# PCB_Source.net
KiCad netlist of a schematic drawn in EasyEDA Pro
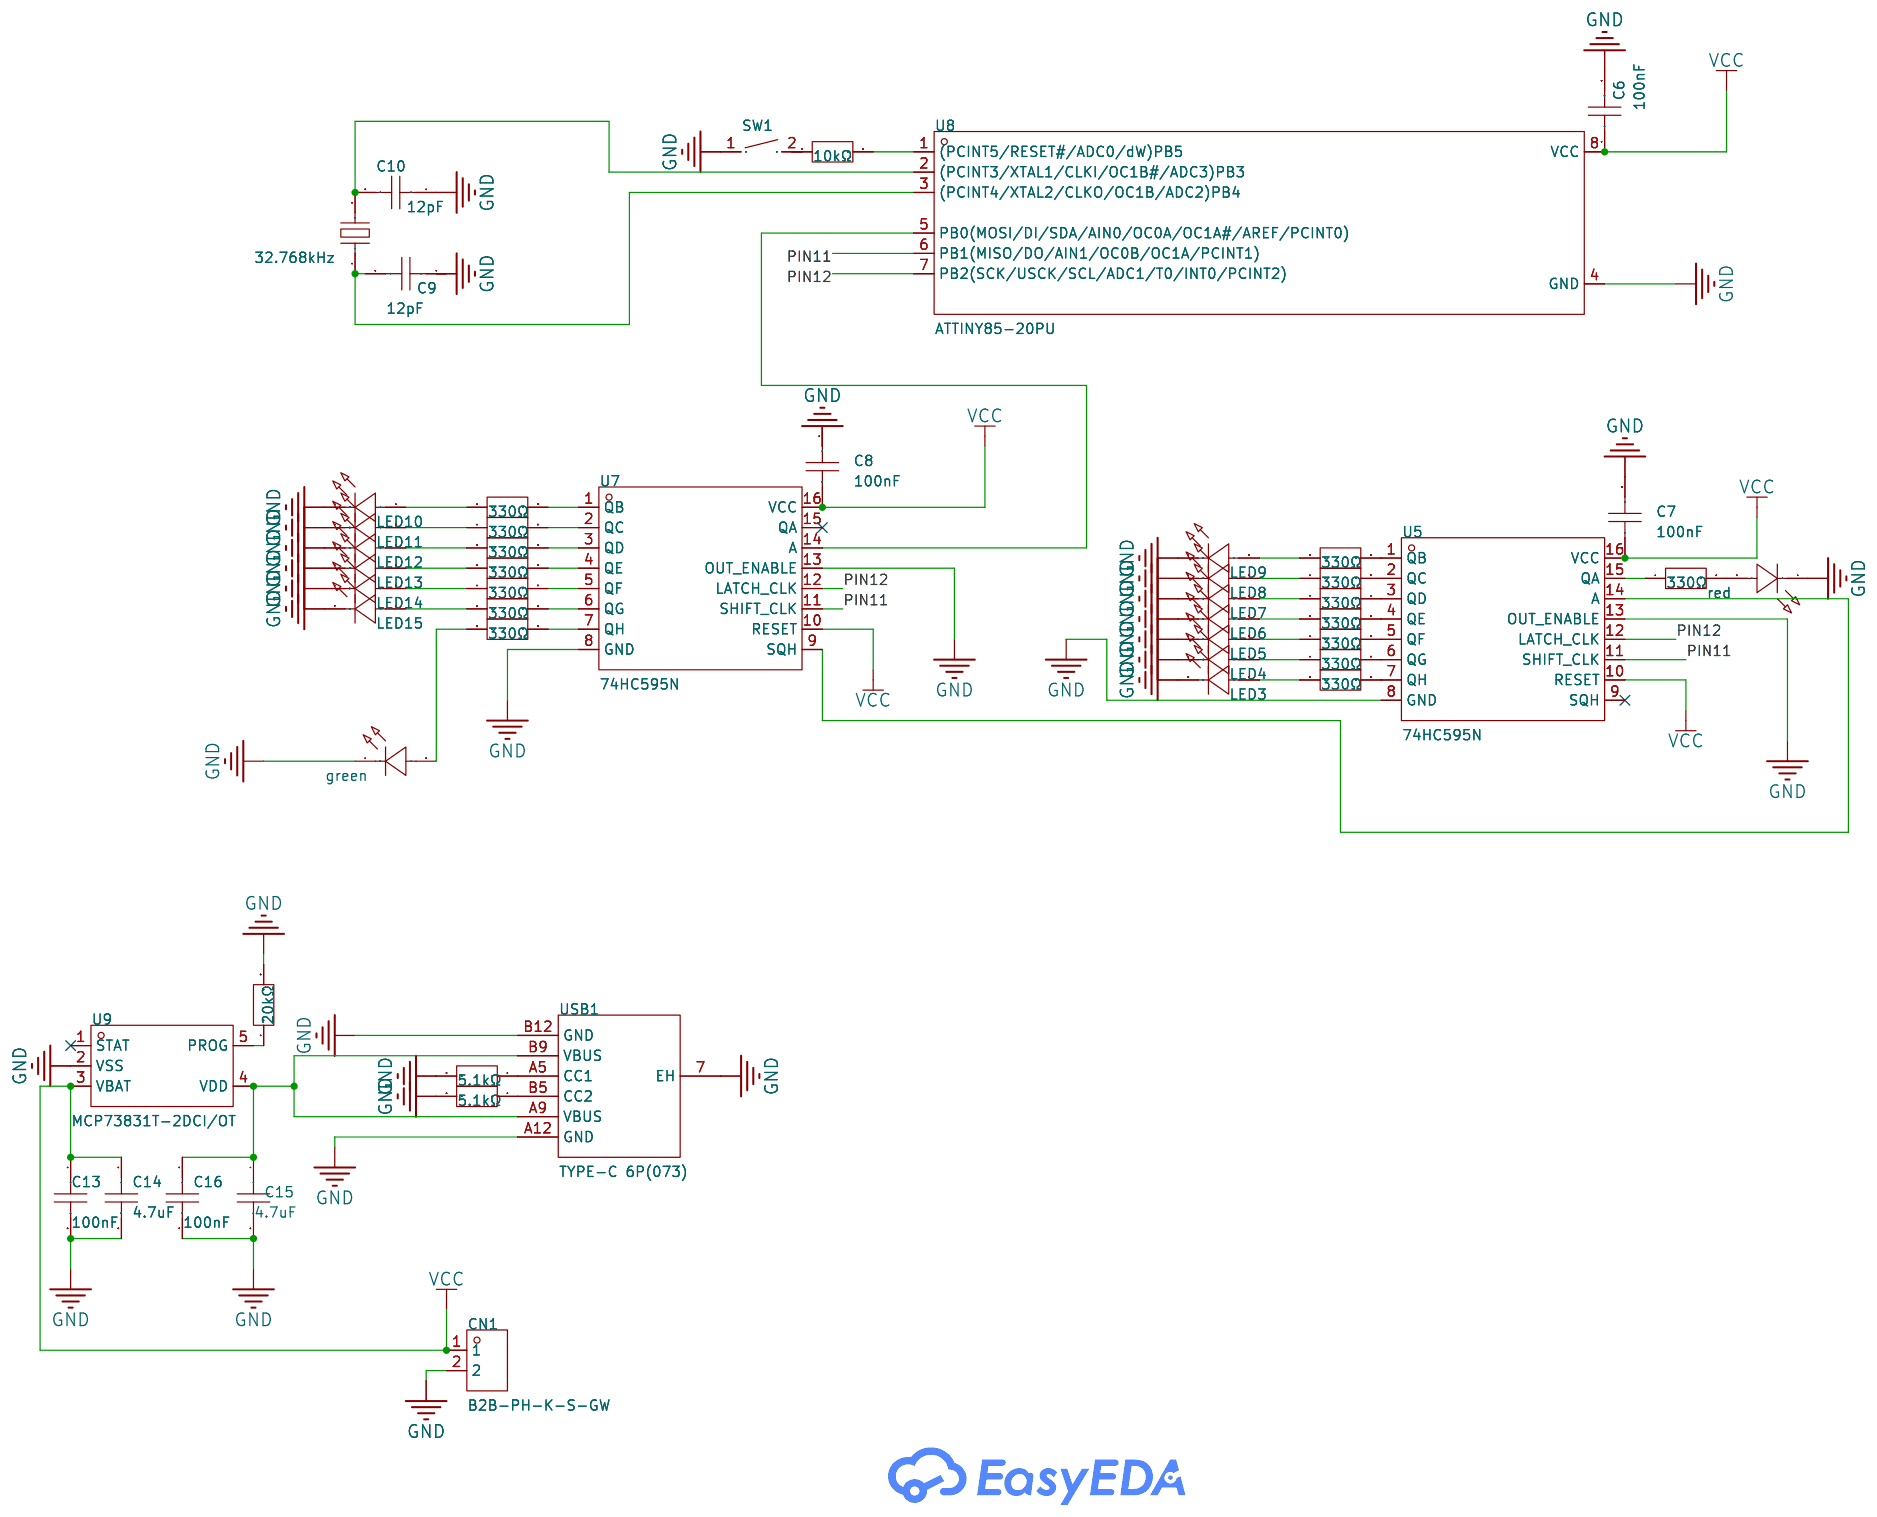
[diagram p0: schematic sheet]

(export (version "E")
  (design (tool "Eeschema 10.0.6"))
  (components
    (comp (ref "C6")
      (value "100nF")
      (footprint "easyedapro:CAP-TH_L5.8-W2.4-P2.54-D0.6")
      (fields
        (field (name "Manufacturer Part") "CC1H104ZA1ED3F5P1100")
        (field (name "Manufacturer") "Dersonic(德尔创)")
      )
      (libsource (lib "easyedapro") (part "CC1H104ZA1ED3F5P1100"))
    )
    (comp (ref "C7")
      (value "100nF")
      (footprint "easyedapro:CAP-TH_L5.8-W2.4-P2.54-D0.6")
      (fields
        (field (name "Manufacturer Part") "CC1H104ZA1ED3F5P1100")
        (field (name "Manufacturer") "Dersonic(德尔创)")
      )
      (libsource (lib "easyedapro") (part "CC1H104ZA1ED3F5P1100"))
    )
    (comp (ref "C8")
      (value "100nF")
      (footprint "easyedapro:CAP-TH_L5.8-W2.4-P2.54-D0.6")
      (fields
        (field (name "Manufacturer Part") "CC1H104ZA1ED3F5P1100")
        (field (name "Manufacturer") "Dersonic(德尔创)")
      )
      (libsource (lib "easyedapro") (part "CC1H104ZA1ED3F5P1100"))
    )
    (comp (ref "C9")
      (value "12pF")
      (footprint "easyedapro:CAP-TH_L5.8-W2.4-P2.54-D0.6")
      (fields
        (field (name "Manufacturer Part") "CC1H104ZA1ED3F5P1100")
        (field (name "Manufacturer") "Dersonic(德尔创)")
      )
      (libsource (lib "easyedapro") (part "CC1H104ZA1ED3F5P1100"))
    )
    (comp (ref "C10")
      (value "12pF")
      (footprint "easyedapro:CAP-TH_L5.8-W2.4-P2.54-D0.6")
      (fields
        (field (name "Manufacturer Part") "CC1H104ZA1ED3F5P1100")
        (field (name "Manufacturer") "Dersonic(德尔创)")
      )
      (libsource (lib "easyedapro") (part "CC1H104ZA1ED3F5P1100"))
    )
    (comp (ref "C13")
      (value "100nF")
      (footprint "easyedapro:CAP-TH_L5.8-W2.4-P2.54-D0.6")
      (fields
        (field (name "Manufacturer Part") "CC1H104ZA1ED3F5P1100")
        (field (name "Manufacturer") "Dersonic(德尔创)")
      )
      (libsource (lib "easyedapro") (part "CC1H104ZA1ED3F5P1100"))
    )
    (comp (ref "C14")
      (value "4.7uF")
      (footprint "easyedapro:CAP-TH_L5.8-W2.4-P2.54-D0.6")
      (fields
        (field (name "Manufacturer Part") "CC1H104ZA1ED3F5P1100")
        (field (name "Manufacturer") "Dersonic(德尔创)")
      )
      (libsource (lib "easyedapro") (part "CC1H104ZA1ED3F5P1100"))
    )
    (comp (ref "C15")
      (value "4.7uF")
      (footprint "easyedapro:CAP-TH_L5.8-W2.4-P2.54-D0.6")
      (fields
        (field (name "Manufacturer Part") "CC1H104ZA1ED3F5P1100")
        (field (name "Manufacturer") "Dersonic(德尔创)")
      )
      (libsource (lib "easyedapro") (part "CC1H104ZA1ED3F5P1100"))
    )
    (comp (ref "C16")
      (value "100nF")
      (footprint "easyedapro:CAP-TH_L5.8-W2.4-P2.54-D0.6")
      (fields
        (field (name "Manufacturer Part") "CC1H104ZA1ED3F5P1100")
        (field (name "Manufacturer") "Dersonic(德尔创)")
      )
      (libsource (lib "easyedapro") (part "CC1H104ZA1ED3F5P1100"))
    )
    (comp (ref "CN1")
      (value "B2B-PH-K-S-GW")
      (footprint "easyedapro:CONN-TH_B2B-PH-K-S")
      (fields (field (name "Manufacturer") "JST"))
      (libsource (lib "easyedapro") (part "B2B-PH-K-S-GW"))
    )
    (comp (ref "green")
      (value "TJ-S2012EX8T5ALC2R-A5")
      (footprint "easyedapro:LED0805-RD")
      (fields (field (name "Manufacturer") "TOGIALED(统佳)"))
      (libsource (lib "easyedapro") (part "TJ-S2012EX8T5ALC2R-A5"))
    )
    (comp (ref "LED3")
      (value "TJ-S2012EX8T5ALC2R-A5")
      (footprint "easyedapro:LED0805-RD")
      (fields (field (name "Manufacturer") "TOGIALED(统佳)"))
      (libsource (lib "easyedapro") (part "TJ-S2012EX8T5ALC2R-A5"))
    )
    (comp (ref "LED4")
      (value "TJ-S2012EX8T5ALC2R-A5")
      (footprint "easyedapro:LED0805-RD")
      (fields (field (name "Manufacturer") "TOGIALED(统佳)"))
      (libsource (lib "easyedapro") (part "TJ-S2012EX8T5ALC2R-A5"))
    )
    (comp (ref "LED5")
      (value "TJ-S2012EX8T5ALC2R-A5")
      (footprint "easyedapro:LED0805-RD")
      (fields (field (name "Manufacturer") "TOGIALED(统佳)"))
      (libsource (lib "easyedapro") (part "TJ-S2012EX8T5ALC2R-A5"))
    )
    (comp (ref "LED6")
      (value "TJ-S2012EX8T5ALC2R-A5")
      (footprint "easyedapro:LED0805-RD")
      (fields (field (name "Manufacturer") "TOGIALED(统佳)"))
      (libsource (lib "easyedapro") (part "TJ-S2012EX8T5ALC2R-A5"))
    )
    (comp (ref "LED7")
      (value "TJ-S2012EX8T5ALC2R-A5")
      (footprint "easyedapro:LED0805-RD")
      (fields (field (name "Manufacturer") "TOGIALED(统佳)"))
      (libsource (lib "easyedapro") (part "TJ-S2012EX8T5ALC2R-A5"))
    )
    (comp (ref "LED8")
      (value "TJ-S2012EX8T5ALC2R-A5")
      (footprint "easyedapro:LED0805-RD")
      (fields (field (name "Manufacturer") "TOGIALED(统佳)"))
      (libsource (lib "easyedapro") (part "TJ-S2012EX8T5ALC2R-A5"))
    )
    (comp (ref "LED9")
      (value "TJ-S2012EX8T5ALC2R-A5")
      (footprint "easyedapro:LED0805-RD")
      (fields (field (name "Manufacturer") "TOGIALED(统佳)"))
      (libsource (lib "easyedapro") (part "TJ-S2012EX8T5ALC2R-A5"))
    )
    (comp (ref "LED10")
      (value "TJ-S2012EX8T5ALC2R-A5")
      (footprint "easyedapro:LED0805-RD")
      (fields (field (name "Manufacturer") "TOGIALED(统佳)"))
      (libsource (lib "easyedapro") (part "TJ-S2012EX8T5ALC2R-A5"))
    )
    (comp (ref "LED11")
      (value "TJ-S2012EX8T5ALC2R-A5")
      (footprint "easyedapro:LED0805-RD")
      (fields (field (name "Manufacturer") "TOGIALED(统佳)"))
      (libsource (lib "easyedapro") (part "TJ-S2012EX8T5ALC2R-A5"))
    )
    (comp (ref "LED12")
      (value "TJ-S2012EX8T5ALC2R-A5")
      (footprint "easyedapro:LED0805-RD")
      (fields (field (name "Manufacturer") "TOGIALED(统佳)"))
      (libsource (lib "easyedapro") (part "TJ-S2012EX8T5ALC2R-A5"))
    )
    (comp (ref "LED13")
      (value "TJ-S2012EX8T5ALC2R-A5")
      (footprint "easyedapro:LED0805-RD")
      (fields (field (name "Manufacturer") "TOGIALED(统佳)"))
      (libsource (lib "easyedapro") (part "TJ-S2012EX8T5ALC2R-A5"))
    )
    (comp (ref "LED14")
      (value "TJ-S2012EX8T5ALC2R-A5")
      (footprint "easyedapro:LED0805-RD")
      (fields (field (name "Manufacturer") "TOGIALED(统佳)"))
      (libsource (lib "easyedapro") (part "TJ-S2012EX8T5ALC2R-A5"))
    )
    (comp (ref "LED15")
      (value "TJ-S2012EX8T5ALC2R-A5")
      (footprint "easyedapro:LED0805-RD")
      (fields (field (name "Manufacturer") "TOGIALED(统佳)"))
      (libsource (lib "easyedapro") (part "TJ-S2012EX8T5ALC2R-A5"))
    )
    (comp (ref "R20")
      (value "330Ω")
      (footprint "easyedapro:RES-TH_BD2.3-L6.5-P10.50-D0.5")
      (fields (field (name "Manufacturer Part") "MF1/4W-1KΩ±1%T52") (field (name "Manufacturer") "华星机电"))
      (libsource (lib "easyedapro") (part "MF1/4W-1KΩ±1%T52"))
    )
    (comp (ref "R21")
      (value "330Ω")
      (footprint "easyedapro:RES-TH_BD2.3-L6.5-P10.50-D0.5")
      (fields (field (name "Manufacturer Part") "MF1/4W-1KΩ±1%T52") (field (name "Manufacturer") "华星机电"))
      (libsource (lib "easyedapro") (part "MF1/4W-1KΩ±1%T52"))
    )
    (comp (ref "R22")
      (value "330Ω")
      (footprint "easyedapro:RES-TH_BD2.3-L6.5-P10.50-D0.5")
      (fields (field (name "Manufacturer Part") "MF1/4W-1KΩ±1%T52") (field (name "Manufacturer") "华星机电"))
      (libsource (lib "easyedapro") (part "MF1/4W-1KΩ±1%T52"))
    )
    (comp (ref "R23")
      (value "330Ω")
      (footprint "easyedapro:RES-TH_BD2.3-L6.5-P10.50-D0.5")
      (fields (field (name "Manufacturer Part") "MF1/4W-1KΩ±1%T52") (field (name "Manufacturer") "华星机电"))
      (libsource (lib "easyedapro") (part "MF1/4W-1KΩ±1%T52"))
    )
    (comp (ref "R24")
      (value "330Ω")
      (footprint "easyedapro:RES-TH_BD2.3-L6.5-P10.50-D0.5")
      (fields (field (name "Manufacturer Part") "MF1/4W-1KΩ±1%T52") (field (name "Manufacturer") "华星机电"))
      (libsource (lib "easyedapro") (part "MF1/4W-1KΩ±1%T52"))
    )
    (comp (ref "R25")
      (value "330Ω")
      (footprint "easyedapro:RES-TH_BD2.3-L6.5-P10.50-D0.5")
      (fields (field (name "Manufacturer Part") "MF1/4W-1KΩ±1%T52") (field (name "Manufacturer") "华星机电"))
      (libsource (lib "easyedapro") (part "MF1/4W-1KΩ±1%T52"))
    )
    (comp (ref "R26")
      (value "330Ω")
      (footprint "easyedapro:RES-TH_BD2.3-L6.5-P10.50-D0.5")
      (fields (field (name "Manufacturer Part") "MF1/4W-1KΩ±1%T52") (field (name "Manufacturer") "华星机电"))
      (libsource (lib "easyedapro") (part "MF1/4W-1KΩ±1%T52"))
    )
    (comp (ref "R27")
      (value "330Ω")
      (footprint "easyedapro:RES-TH_BD2.3-L6.5-P10.50-D0.5")
      (fields (field (name "Manufacturer Part") "MF1/4W-1KΩ±1%T52") (field (name "Manufacturer") "华星机电"))
      (libsource (lib "easyedapro") (part "MF1/4W-1KΩ±1%T52"))
    )
    (comp (ref "R28")
      (value "330Ω")
      (footprint "easyedapro:RES-TH_BD2.3-L6.5-P10.50-D0.5")
      (fields (field (name "Manufacturer Part") "MF1/4W-1KΩ±1%T52") (field (name "Manufacturer") "华星机电"))
      (libsource (lib "easyedapro") (part "MF1/4W-1KΩ±1%T52"))
    )
    (comp (ref "R29")
      (value "330Ω")
      (footprint "easyedapro:RES-TH_BD2.3-L6.5-P10.50-D0.5")
      (fields (field (name "Manufacturer Part") "MF1/4W-1KΩ±1%T52") (field (name "Manufacturer") "华星机电"))
      (libsource (lib "easyedapro") (part "MF1/4W-1KΩ±1%T52"))
    )
    (comp (ref "R30")
      (value "330Ω")
      (footprint "easyedapro:RES-TH_BD2.3-L6.5-P10.50-D0.5")
      (fields (field (name "Manufacturer Part") "MF1/4W-1KΩ±1%T52") (field (name "Manufacturer") "华星机电"))
      (libsource (lib "easyedapro") (part "MF1/4W-1KΩ±1%T52"))
    )
    (comp (ref "R31")
      (value "330Ω")
      (footprint "easyedapro:RES-TH_BD2.3-L6.5-P10.50-D0.5")
      (fields (field (name "Manufacturer Part") "MF1/4W-1KΩ±1%T52") (field (name "Manufacturer") "华星机电"))
      (libsource (lib "easyedapro") (part "MF1/4W-1KΩ±1%T52"))
    )
    (comp (ref "R32")
      (value "330Ω")
      (footprint "easyedapro:RES-TH_BD2.3-L6.5-P10.50-D0.5")
      (fields (field (name "Manufacturer Part") "MF1/4W-1KΩ±1%T52") (field (name "Manufacturer") "华星机电"))
      (libsource (lib "easyedapro") (part "MF1/4W-1KΩ±1%T52"))
    )
    (comp (ref "R33")
      (value "330Ω")
      (footprint "easyedapro:RES-TH_BD2.3-L6.5-P10.50-D0.5")
      (fields (field (name "Manufacturer Part") "MF1/4W-1KΩ±1%T52") (field (name "Manufacturer") "华星机电"))
      (libsource (lib "easyedapro") (part "MF1/4W-1KΩ±1%T52"))
    )
    (comp (ref "R34")
      (value "330Ω")
      (footprint "easyedapro:RES-TH_BD2.3-L6.5-P10.50-D0.5")
      (fields (field (name "Manufacturer Part") "MF1/4W-1KΩ±1%T52") (field (name "Manufacturer") "华星机电"))
      (libsource (lib "easyedapro") (part "MF1/4W-1KΩ±1%T52"))
    )
    (comp (ref "R36")
      (value "10kΩ")
      (footprint "easyedapro:RES-TH_BD2.3-L6.5-P10.50-D0.5")
      (fields (field (name "Manufacturer Part") "MF1/4W-1KΩ±1%T52") (field (name "Manufacturer") "华星机电"))
      (libsource (lib "easyedapro") (part "MF1/4W-1KΩ±1%T52"))
    )
    (comp (ref "R40")
      (value "20kΩ")
      (footprint "easyedapro:RES-TH_BD2.3-L6.5-P10.50-D0.5")
      (fields (field (name "Manufacturer Part") "MF1/4W-1KΩ±1%T52") (field (name "Manufacturer") "华星机电"))
      (libsource (lib "easyedapro") (part "MF1/4W-1KΩ±1%T52"))
    )
    (comp (ref "R41")
      (value "5.1kΩ")
      (footprint "easyedapro:RES-TH_BD2.3-L6.5-P10.50-D0.5")
      (fields (field (name "Manufacturer Part") "MF1/4W-1KΩ±1%T52") (field (name "Manufacturer") "华星机电"))
      (libsource (lib "easyedapro") (part "MF1/4W-1KΩ±1%T52"))
    )
    (comp (ref "R42")
      (value "5.1kΩ")
      (footprint "easyedapro:RES-TH_BD2.3-L6.5-P10.50-D0.5")
      (fields (field (name "Manufacturer Part") "MF1/4W-1KΩ±1%T52") (field (name "Manufacturer") "华星机电"))
      (libsource (lib "easyedapro") (part "MF1/4W-1KΩ±1%T52"))
    )
    (comp (ref "red")
      (value "TJ-S2012EX8T5ALC2R-A5")
      (footprint "easyedapro:LED0805-RD")
      (fields (field (name "Manufacturer") "TOGIALED(统佳)"))
      (libsource (lib "easyedapro") (part "TJ-S2012EX8T5ALC2R-A5"))
    )
    (comp (ref "SW1")
      (value "HX 3x4x2-2P-1.6N TACTILE SWITCH")
      (footprint "easyedapro:KEY-SMD_L4.0-W3.0-LS4.9-1")
      (fields (field (name "Manufacturer") "hanxia(韩下)"))
      (libsource (lib "easyedapro") (part "HX 3X4X2-2P-1.6N TACTILE SWITCH"))
    )
    (comp (ref "U5")
      (value "74HC595N")
      (footprint "easyedapro:DIP-16_L19.8-W6.5-P2.54-LS7.6-BL")
      (fields (field (name "Manufacturer") "HTC"))
      (libsource (lib "easyedapro") (part "74HC595N_C669328"))
    )
    (comp (ref "U7")
      (value "74HC595N")
      (footprint "easyedapro:DIP-16_L19.8-W6.5-P2.54-LS7.6-BL")
      (fields (field (name "Manufacturer") "HTC"))
      (libsource (lib "easyedapro") (part "74HC595N_C669328"))
    )
    (comp (ref "U8")
      (value "ATTINY85-20PU")
      (footprint "easyedapro:PDIP-8_L9.3-W6.4-P2.54-LS7.9-BL-1")
      (fields (field (name "Manufacturer") "MICROCHIP(美国微芯)"))
      (libsource (lib "easyedapro") (part "ATTINY85-20PU"))
    )
    (comp (ref "U9")
      (value "MCP73831T-2DCI/OT")
      (footprint "easyedapro:SOT-23-5_L2.9-W1.6-P0.95-LS2.8-BL")
      (fields (field (name "Manufacturer") "MICROCHIP(美国微芯)"))
      (libsource (lib "easyedapro") (part "MCP73831T-2DCI/OT"))
    )
    (comp (ref "USB1")
      (value "TYPE-C 6P(073)")
      (footprint "easyedapro:TYPE-C-SMD_TYPE-C-6P-073")
      (fields (field (name "Manufacturer") "SHOU HAN(首韩)"))
      (libsource (lib "easyedapro") (part "TYPE-C 6P(073)"))
    )
    (comp (ref "X1")
      (value "32.768kHz")
      (footprint "easyedapro:OSC-TH_BD2.0-P0.70-D0.3")
      (fields
        (field (name "Manufacturer Part") "TAXD32768K2BGBBZT2S")
        (field (name "Manufacturer") "YJX(雅晶鑫)")
      )
      (libsource (lib "easyedapro") (part "TAXD32768K2BGBBZT2S"))
    )
  )
  (nets
    (net (code "1") (name "/PIN11") (class "Default")
      (node (ref "U5") (pin "11") (pinfunction "SHIFT_CLK_11") (pintype "unspecified"))
      (node (ref "U7") (pin "11") (pinfunction "SHIFT_CLK_11") (pintype "unspecified"))
      (node (ref "U8") (pin "6") (pinfunction "PB1(MISO/DO/AIN1/OC0B/OC1A/PCINT1)_6") (pintype "unspecified"))
    )
    (net (code "2") (name "/PIN12") (class "Default")
      (node (ref "U5") (pin "12") (pinfunction "LATCH_CLK_12") (pintype "unspecified"))
      (node (ref "U7") (pin "12") (pinfunction "LATCH_CLK_12") (pintype "unspecified"))
      (node (ref "U8") (pin "7") (pinfunction "PB2(SCK/USCK/SCL/ADC1/T0/INT0/PCINT2)_7") (pintype "unspecified"))
    )
    (net (code "3") (name "GND") (class "Default")
      (node (ref "C10") (pin "1") (pinfunction "1_1") (pintype "unspecified"))
      (node (ref "C13") (pin "2") (pinfunction "2_2") (pintype "unspecified"))
      (node (ref "C14") (pin "2") (pinfunction "2_2") (pintype "unspecified"))
      (node (ref "C15") (pin "2") (pinfunction "2_2") (pintype "unspecified"))
      (node (ref "C16") (pin "2") (pinfunction "2_2") (pintype "unspecified"))
      (node (ref "C6") (pin "2") (pinfunction "2_2") (pintype "unspecified"))
      (node (ref "C7") (pin "2") (pinfunction "2_2") (pintype "unspecified"))
      (node (ref "C8") (pin "1") (pinfunction "1_1") (pintype "unspecified"))
      (node (ref "C9") (pin "1") (pinfunction "1_1") (pintype "unspecified"))
      (node (ref "CN1") (pin "2") (pinfunction "2_2") (pintype "unspecified"))
      (node (ref "LED10") (pin "1") (pinfunction "C_1") (pintype "unspecified"))
      (node (ref "LED11") (pin "1") (pinfunction "C_1") (pintype "unspecified"))
      (node (ref "LED12") (pin "1") (pinfunction "C_1") (pintype "unspecified"))
      (node (ref "LED13") (pin "1") (pinfunction "C_1") (pintype "unspecified"))
      (node (ref "LED14") (pin "1") (pinfunction "C_1") (pintype "unspecified"))
      (node (ref "LED15") (pin "1") (pinfunction "C_1") (pintype "unspecified"))
      (node (ref "LED3") (pin "1") (pinfunction "C_1") (pintype "unspecified"))
      (node (ref "LED4") (pin "1") (pinfunction "C_1") (pintype "unspecified"))
      (node (ref "LED5") (pin "1") (pinfunction "C_1") (pintype "unspecified"))
      (node (ref "LED6") (pin "1") (pinfunction "C_1") (pintype "unspecified"))
      (node (ref "LED7") (pin "1") (pinfunction "C_1") (pintype "unspecified"))
      (node (ref "LED8") (pin "1") (pinfunction "C_1") (pintype "unspecified"))
      (node (ref "LED9") (pin "1") (pinfunction "C_1") (pintype "unspecified"))
      (node (ref "R40") (pin "2") (pinfunction "2_2") (pintype "unspecified"))
      (node (ref "R41") (pin "2") (pinfunction "2_2") (pintype "unspecified"))
      (node (ref "R42") (pin "2") (pinfunction "2_2") (pintype "unspecified"))
      (node (ref "SW1") (pin "1") (pinfunction "1_1") (pintype "unspecified"))
      (node (ref "U5") (pin "13") (pinfunction "OUT_ENABLE_13") (pintype "unspecified"))
      (node (ref "U5") (pin "8") (pinfunction "GND_8") (pintype "unspecified"))
      (node (ref "U7") (pin "13") (pinfunction "OUT_ENABLE_13") (pintype "unspecified"))
      (node (ref "U7") (pin "8") (pinfunction "GND_8") (pintype "unspecified"))
      (node (ref "U8") (pin "4") (pinfunction "GND_4") (pintype "unspecified"))
      (node (ref "U9") (pin "2") (pinfunction "VSS_2") (pintype "unspecified"))
      (node (ref "USB1") (pin "7") (pinfunction "EH_7") (pintype "unspecified"))
      (node (ref "USB1") (pin "A12") (pinfunction "GND_A12") (pintype "unspecified"))
      (node (ref "USB1") (pin "B12") (pinfunction "GND_B12") (pintype "unspecified"))
      (node (ref "green") (pin "1") (pinfunction "C_1") (pintype "unspecified"))
      (node (ref "red") (pin "1") (pinfunction "C_1") (pintype "unspecified"))
    )
    (net (code "4") (name "Net-(LED3-A)") (class "Default")
      (node (ref "LED3") (pin "2") (pinfunction "A_2") (pintype "unspecified"))
      (node (ref "R33") (pin "1") (pinfunction "1_1") (pintype "unspecified"))
    )
    (net (code "5") (name "Net-(LED4-A)") (class "Default")
      (node (ref "LED4") (pin "2") (pinfunction "A_2") (pintype "unspecified"))
      (node (ref "R32") (pin "1") (pinfunction "1_1") (pintype "unspecified"))
    )
    (net (code "6") (name "Net-(LED5-A)") (class "Default")
      (node (ref "LED5") (pin "2") (pinfunction "A_2") (pintype "unspecified"))
      (node (ref "R31") (pin "1") (pinfunction "1_1") (pintype "unspecified"))
    )
    (net (code "7") (name "Net-(LED6-A)") (class "Default")
      (node (ref "LED6") (pin "2") (pinfunction "A_2") (pintype "unspecified"))
      (node (ref "R30") (pin "1") (pinfunction "1_1") (pintype "unspecified"))
    )
    (net (code "8") (name "Net-(LED7-A)") (class "Default")
      (node (ref "LED7") (pin "2") (pinfunction "A_2") (pintype "unspecified"))
      (node (ref "R29") (pin "1") (pinfunction "1_1") (pintype "unspecified"))
    )
    (net (code "9") (name "Net-(LED8-A)") (class "Default")
      (node (ref "LED8") (pin "2") (pinfunction "A_2") (pintype "unspecified"))
      (node (ref "R28") (pin "1") (pinfunction "1_1") (pintype "unspecified"))
    )
    (net (code "10") (name "Net-(LED9-A)") (class "Default")
      (node (ref "LED9") (pin "2") (pinfunction "A_2") (pintype "unspecified"))
      (node (ref "R27") (pin "1") (pinfunction "1_1") (pintype "unspecified"))
    )
    (net (code "11") (name "Net-(LED10-A)") (class "Default")
      (node (ref "LED10") (pin "2") (pinfunction "A_2") (pintype "unspecified"))
      (node (ref "R20") (pin "1") (pinfunction "1_1") (pintype "unspecified"))
    )
    (net (code "12") (name "Net-(LED11-A)") (class "Default")
      (node (ref "LED11") (pin "2") (pinfunction "A_2") (pintype "unspecified"))
      (node (ref "R21") (pin "1") (pinfunction "1_1") (pintype "unspecified"))
    )
    (net (code "13") (name "Net-(LED12-A)") (class "Default")
      (node (ref "LED12") (pin "2") (pinfunction "A_2") (pintype "unspecified"))
      (node (ref "R22") (pin "1") (pinfunction "1_1") (pintype "unspecified"))
    )
    (net (code "14") (name "Net-(LED13-A)") (class "Default")
      (node (ref "LED13") (pin "2") (pinfunction "A_2") (pintype "unspecified"))
      (node (ref "R23") (pin "1") (pinfunction "1_1") (pintype "unspecified"))
    )
    (net (code "15") (name "Net-(LED14-A)") (class "Default")
      (node (ref "LED14") (pin "2") (pinfunction "A_2") (pintype "unspecified"))
      (node (ref "R24") (pin "1") (pinfunction "1_1") (pintype "unspecified"))
    )
    (net (code "16") (name "Net-(LED15-A)") (class "Default")
      (node (ref "LED15") (pin "2") (pinfunction "A_2") (pintype "unspecified"))
      (node (ref "R25") (pin "1") (pinfunction "1_1") (pintype "unspecified"))
    )
    (net (code "17") (name "Net-(R36-Pad1)") (class "Default")
      (node (ref "R36") (pin "1") (pinfunction "1_1") (pintype "unspecified"))
      (node (ref "SW1") (pin "2") (pinfunction "2_2") (pintype "unspecified"))
    )
    (net (code "18") (name "Net-(U5-A)") (class "Default")
      (node (ref "U5") (pin "14") (pinfunction "A_14") (pintype "unspecified"))
      (node (ref "U7") (pin "9") (pinfunction "SQH_9") (pintype "unspecified"))
    )
    (net (code "19") (name "Net-(U5-QA)") (class "Default")
      (node (ref "R34") (pin "1") (pinfunction "1_1") (pintype "unspecified"))
      (node (ref "U5") (pin "15") (pinfunction "QA_15") (pintype "unspecified"))
    )
    (net (code "20") (name "Net-(U5-QB)") (class "Default")
      (node (ref "R27") (pin "2") (pinfunction "2_2") (pintype "unspecified"))
      (node (ref "U5") (pin "1") (pinfunction "QB_1") (pintype "unspecified"))
    )
    (net (code "21") (name "Net-(U5-QC)") (class "Default")
      (node (ref "R28") (pin "2") (pinfunction "2_2") (pintype "unspecified"))
      (node (ref "U5") (pin "2") (pinfunction "QC_2") (pintype "unspecified"))
    )
    (net (code "22") (name "Net-(U5-QD)") (class "Default")
      (node (ref "R29") (pin "2") (pinfunction "2_2") (pintype "unspecified"))
      (node (ref "U5") (pin "3") (pinfunction "QD_3") (pintype "unspecified"))
    )
    (net (code "23") (name "Net-(U5-QE)") (class "Default")
      (node (ref "R30") (pin "2") (pinfunction "2_2") (pintype "unspecified"))
      (node (ref "U5") (pin "4") (pinfunction "QE_4") (pintype "unspecified"))
    )
    (net (code "24") (name "Net-(U5-QF)") (class "Default")
      (node (ref "R31") (pin "2") (pinfunction "2_2") (pintype "unspecified"))
      (node (ref "U5") (pin "5") (pinfunction "QF_5") (pintype "unspecified"))
    )
    (net (code "25") (name "Net-(U5-QG)") (class "Default")
      (node (ref "R32") (pin "2") (pinfunction "2_2") (pintype "unspecified"))
      (node (ref "U5") (pin "6") (pinfunction "QG_6") (pintype "unspecified"))
    )
    (net (code "26") (name "Net-(U5-QH)") (class "Default")
      (node (ref "R33") (pin "2") (pinfunction "2_2") (pintype "unspecified"))
      (node (ref "U5") (pin "7") (pinfunction "QH_7") (pintype "unspecified"))
    )
    (net (code "27") (name "Net-(U7-A)") (class "Default")
      (node (ref "U7") (pin "14") (pinfunction "A_14") (pintype "unspecified"))
      (node (ref "U8") (pin "5") (pinfunction "PB0(MOSI/DI/SDA/AIN0/OC0A/OC1A#/AREF/PCINT0)_5") (pintype "unspecified"))
    )
    (net (code "28") (name "Net-(U7-QB)") (class "Default")
      (node (ref "R20") (pin "2") (pinfunction "2_2") (pintype "unspecified"))
      (node (ref "U7") (pin "1") (pinfunction "QB_1") (pintype "unspecified"))
    )
    (net (code "29") (name "Net-(U7-QC)") (class "Default")
      (node (ref "R21") (pin "2") (pinfunction "2_2") (pintype "unspecified"))
      (node (ref "U7") (pin "2") (pinfunction "QC_2") (pintype "unspecified"))
    )
    (net (code "30") (name "Net-(U7-QD)") (class "Default")
      (node (ref "R22") (pin "2") (pinfunction "2_2") (pintype "unspecified"))
      (node (ref "U7") (pin "3") (pinfunction "QD_3") (pintype "unspecified"))
    )
    (net (code "31") (name "Net-(U7-QE)") (class "Default")
      (node (ref "R23") (pin "2") (pinfunction "2_2") (pintype "unspecified"))
      (node (ref "U7") (pin "4") (pinfunction "QE_4") (pintype "unspecified"))
    )
    (net (code "32") (name "Net-(U7-QF)") (class "Default")
      (node (ref "R24") (pin "2") (pinfunction "2_2") (pintype "unspecified"))
      (node (ref "U7") (pin "5") (pinfunction "QF_5") (pintype "unspecified"))
    )
    (net (code "33") (name "Net-(U7-QG)") (class "Default")
      (node (ref "R25") (pin "2") (pinfunction "2_2") (pintype "unspecified"))
      (node (ref "U7") (pin "6") (pinfunction "QG_6") (pintype "unspecified"))
    )
    (net (code "34") (name "Net-(U7-QH)") (class "Default")
      (node (ref "R26") (pin "2") (pinfunction "2_2") (pintype "unspecified"))
      (node (ref "U7") (pin "7") (pinfunction "QH_7") (pintype "unspecified"))
    )
    (net (code "35") (name "Net-(U8-(PCINT3{slash}XTAL1{slash}CLKI{slash}OC1B#{slash}ADC3)PB3)") (class "Default")
      (node (ref "C10") (pin "2") (pinfunction "2_2") (pintype "unspecified"))
      (node (ref "U8") (pin "2") (pinfunction "(PCINT3/XTAL1/CLKI/OC1B#/ADC3)PB3_2") (pintype "unspecified"))
      (node (ref "X1") (pin "2") (pinfunction "2_2") (pintype "input"))
    )
    (net (code "36") (name "Net-(U8-(PCINT4{slash}XTAL2{slash}CLKO{slash}OC1B{slash}ADC2)PB4)") (class "Default")
      (node (ref "C9") (pin "2") (pinfunction "2_2") (pintype "unspecified"))
      (node (ref "U8") (pin "3") (pinfunction "(PCINT4/XTAL2/CLKO/OC1B/ADC2)PB4_3") (pintype "unspecified"))
      (node (ref "X1") (pin "1") (pinfunction "1_1") (pintype "input"))
    )
    (net (code "37") (name "Net-(U8-(PCINT5{slash}RESET#{slash}ADC0{slash}dW)PB5)") (class "Default")
      (node (ref "R36") (pin "2") (pinfunction "2_2") (pintype "unspecified"))
      (node (ref "U8") (pin "1") (pinfunction "(PCINT5/RESET#/ADC0/dW)PB5_1") (pintype "unspecified"))
    )
    (net (code "38") (name "Net-(U9-PROG)") (class "Default")
      (node (ref "R40") (pin "1") (pinfunction "1_1") (pintype "unspecified"))
      (node (ref "U9") (pin "5") (pinfunction "PROG_5") (pintype "unspecified"))
    )
    (net (code "39") (name "Net-(U9-VDD)") (class "Default")
      (node (ref "C15") (pin "1") (pinfunction "1_1") (pintype "unspecified"))
      (node (ref "C16") (pin "1") (pinfunction "1_1") (pintype "unspecified"))
      (node (ref "U9") (pin "4") (pinfunction "VDD_4") (pintype "unspecified"))
      (node (ref "USB1") (pin "A9") (pinfunction "VBUS_A9") (pintype "unspecified"))
      (node (ref "USB1") (pin "B9") (pinfunction "VBUS_B9") (pintype "unspecified"))
    )
    (net (code "40") (name "Net-(USB1-CC1)") (class "Default")
      (node (ref "R41") (pin "1") (pinfunction "1_1") (pintype "unspecified"))
      (node (ref "USB1") (pin "A5") (pinfunction "CC1_A5") (pintype "unspecified"))
    )
    (net (code "41") (name "Net-(USB1-CC2)") (class "Default")
      (node (ref "R42") (pin "1") (pinfunction "1_1") (pintype "unspecified"))
      (node (ref "USB1") (pin "B5") (pinfunction "CC2_B5") (pintype "unspecified"))
    )
    (net (code "42") (name "Net-(green-A)") (class "Default")
      (node (ref "R26") (pin "1") (pinfunction "1_1") (pintype "unspecified"))
      (node (ref "green") (pin "2") (pinfunction "A_2") (pintype "unspecified"))
    )
    (net (code "43") (name "Net-(red-A)") (class "Default")
      (node (ref "R34") (pin "2") (pinfunction "2_2") (pintype "unspecified"))
      (node (ref "red") (pin "2") (pinfunction "A_2") (pintype "unspecified"))
    )
    (net (code "44") (name "VCC") (class "Default")
      (node (ref "C13") (pin "1") (pinfunction "1_1") (pintype "unspecified"))
      (node (ref "C14") (pin "1") (pinfunction "1_1") (pintype "unspecified"))
      (node (ref "C6") (pin "1") (pinfunction "1_1") (pintype "unspecified"))
      (node (ref "C7") (pin "1") (pinfunction "1_1") (pintype "unspecified"))
      (node (ref "C8") (pin "2") (pinfunction "2_2") (pintype "unspecified"))
      (node (ref "CN1") (pin "1") (pinfunction "1_1") (pintype "unspecified"))
      (node (ref "U5") (pin "10") (pinfunction "RESET_10") (pintype "unspecified"))
      (node (ref "U5") (pin "16") (pinfunction "VCC_16") (pintype "unspecified"))
      (node (ref "U7") (pin "10") (pinfunction "RESET_10") (pintype "unspecified"))
      (node (ref "U7") (pin "16") (pinfunction "VCC_16") (pintype "unspecified"))
      (node (ref "U8") (pin "8") (pinfunction "VCC_8") (pintype "unspecified"))
      (node (ref "U9") (pin "3") (pinfunction "VBAT_3") (pintype "unspecified"))
    )
    (net (code "45") (name "unconnected-(U5-SQH-Pad9)") (class "Default")
      (node (ref "U5") (pin "9") (pinfunction "SQH_9") (pintype "unspecified+no_connect"))
    )
    (net (code "46") (name "unconnected-(U7-QA-Pad15)") (class "Default")
      (node (ref "U7") (pin "15") (pinfunction "QA_15") (pintype "unspecified+no_connect"))
    )
    (net (code "47") (name "unconnected-(U9-STAT-Pad1)") (class "Default")
      (node (ref "U9") (pin "1") (pinfunction "STAT_1") (pintype "unspecified+no_connect"))
    )
  )
)
